# Sheet.net
KiCad netlist of a schematic drawn in Altium Designer
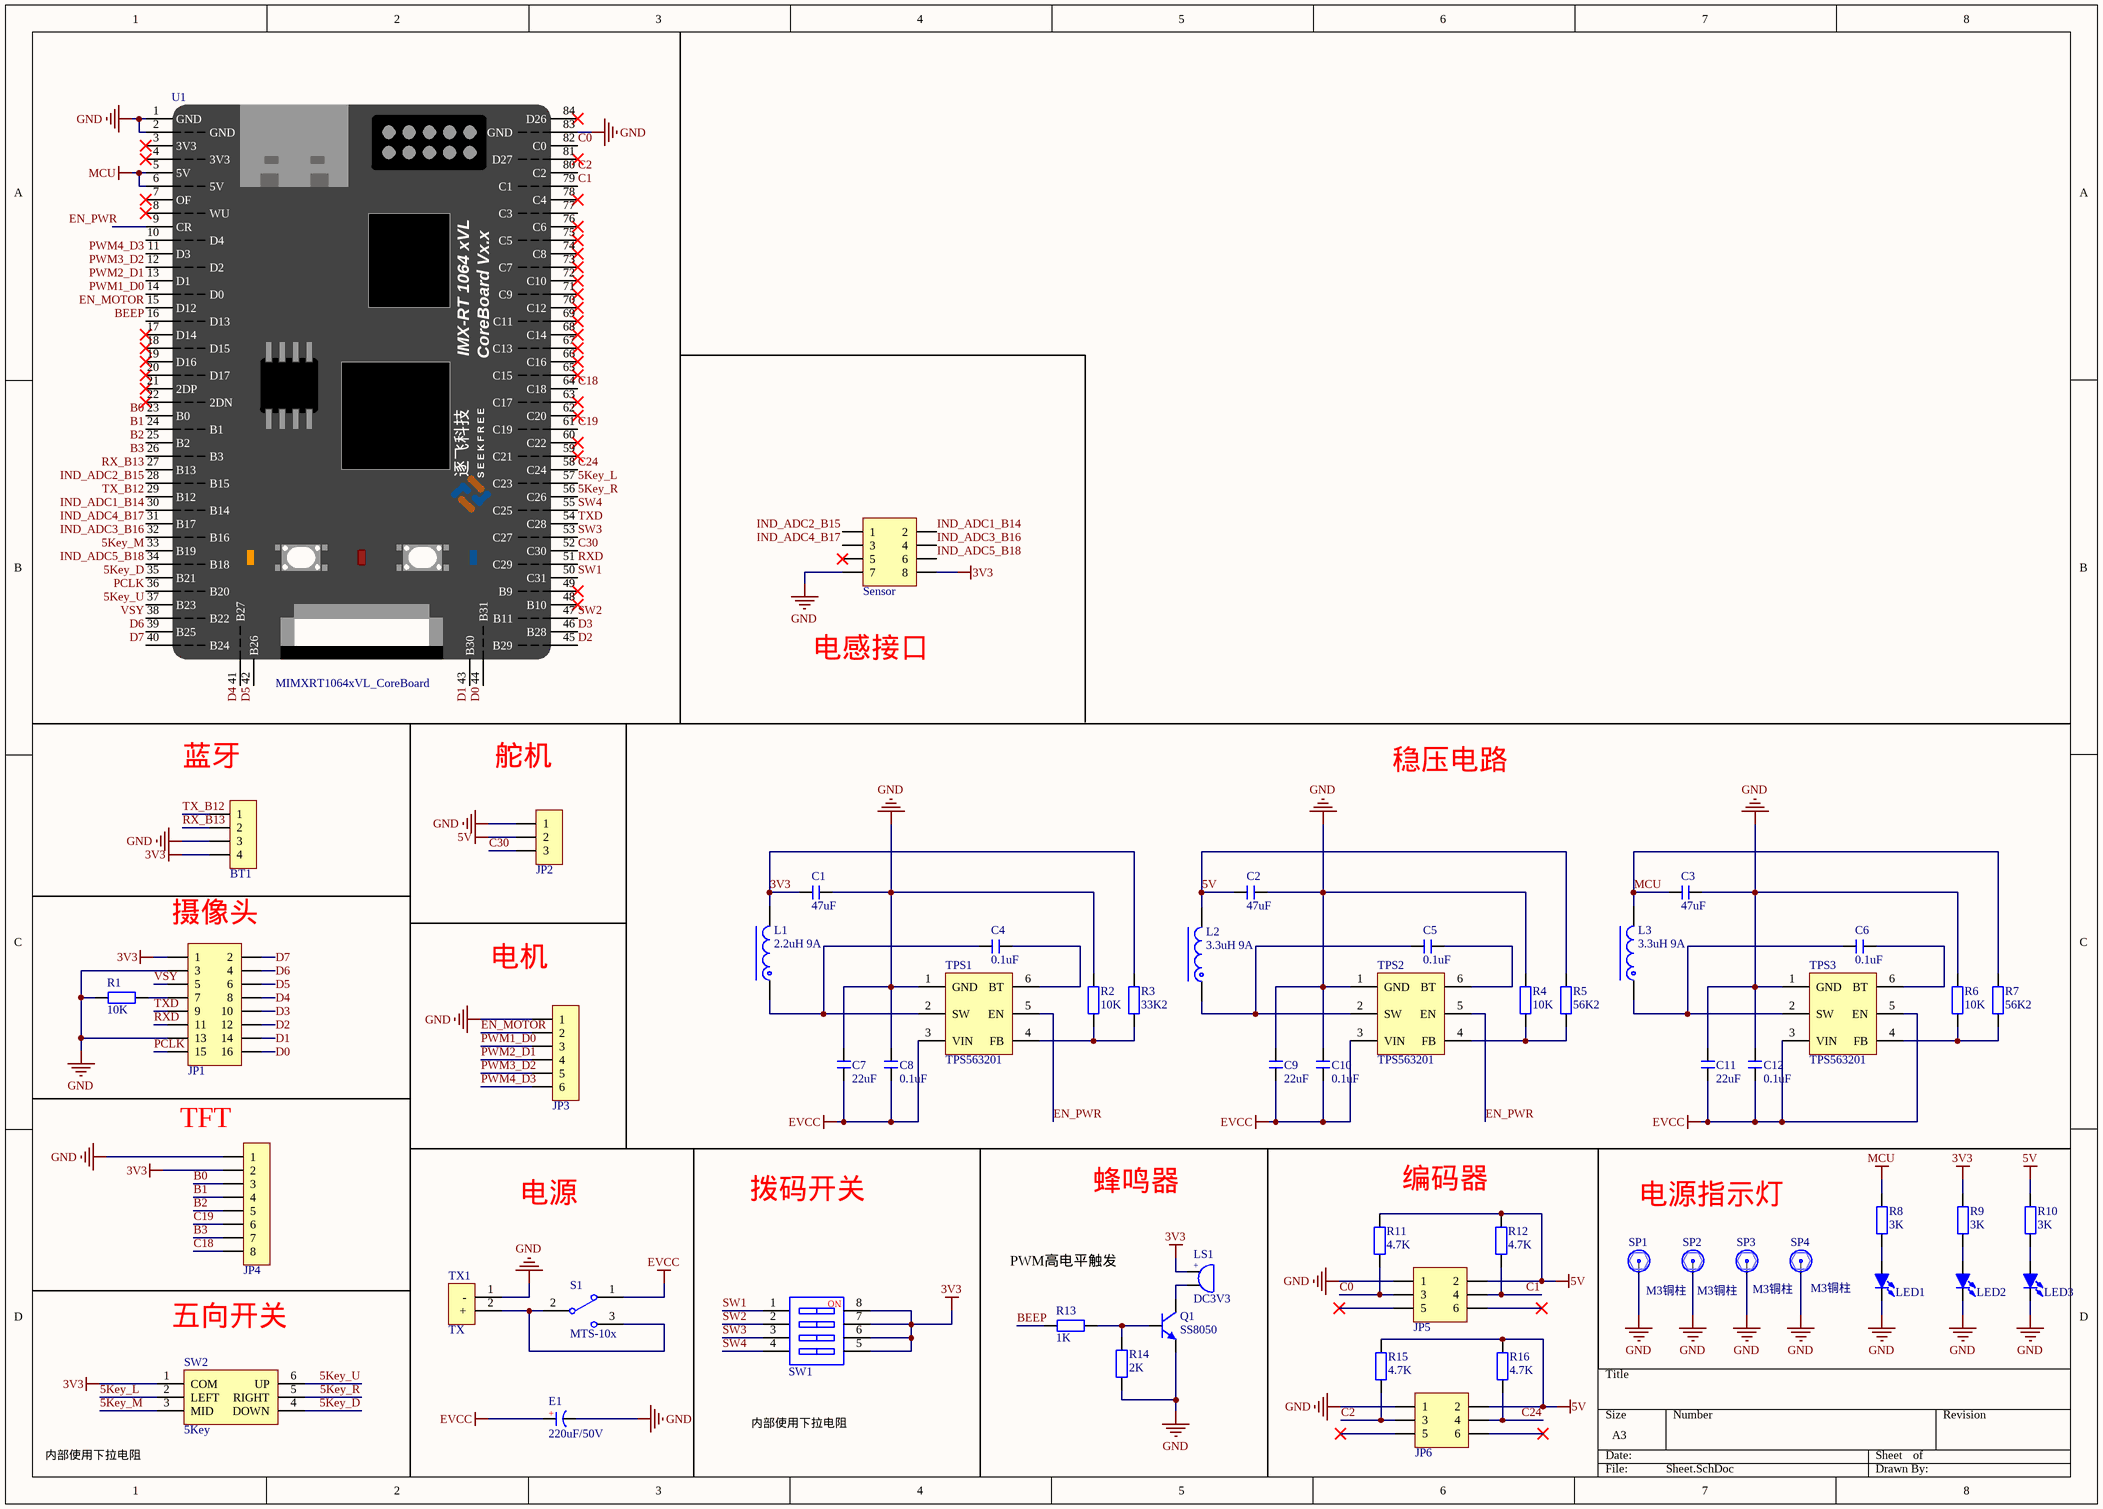
[diagram p0: Sheet.SchDoc]

(export (version "E")
  (design (tool "Eeschema 10.0.6"))
  (components
    (comp (ref "BT1")
      (value "HDR-1X4")
      (footprint "HDR2.54-M-LI-4P")
      (description "4P接插件")
      (fields (field (name "版权归属") "源创客"))
      (libsource (lib "Schlib") (part "Header 4"))
    )
    (comp (ref "C1")
      (value "47uF")
      (footprint "C 1206_M")
      (description "无极性贴片电容")
      (fields (field (name "版权归属") "源创客"))
      (libsource (lib "Schlib") (part "C_2"))
    )
    (comp (ref "C2")
      (value "47uF")
      (footprint "C 1206_M")
      (description "无极性贴片电容")
      (fields (field (name "版权归属") "源创客"))
      (libsource (lib "Schlib") (part "C_2"))
    )
    (comp (ref "C3")
      (value "47uF")
      (footprint "C 1206_M")
      (description "无极性贴片电容")
      (fields (field (name "版权归属") "源创客"))
      (libsource (lib "Schlib") (part "C_2"))
    )
    (comp (ref "C4")
      (value "0.1uF")
      (footprint "C 0603_M")
      (description "无极性贴片电容")
      (fields (field (name "版权归属") "源创客"))
      (libsource (lib "Schlib") (part "C_1"))
    )
    (comp (ref "C5")
      (value "0.1uF")
      (footprint "C 0603_M")
      (description "无极性贴片电容")
      (fields (field (name "版权归属") "源创客"))
      (libsource (lib "Schlib") (part "C_1"))
    )
    (comp (ref "C6")
      (value "0.1uF")
      (footprint "C 0603_M")
      (description "无极性贴片电容")
      (fields (field (name "版权归属") "源创客"))
      (libsource (lib "Schlib") (part "C_1"))
    )
    (comp (ref "C7")
      (value "22uF")
      (footprint "C 1206_M")
      (description "无极性贴片电容")
      (fields (field (name "版权归属") "源创客"))
      (libsource (lib "Schlib") (part "C"))
    )
    (comp (ref "C8")
      (value "0.1uF")
      (footprint "C 0603_M")
      (description "无极性贴片电容")
      (fields (field (name "版权归属") "源创客"))
      (libsource (lib "Schlib") (part "C_1"))
    )
    (comp (ref "C9")
      (value "22uF")
      (footprint "C 1206_M")
      (description "无极性贴片电容")
      (fields (field (name "版权归属") "源创客"))
      (libsource (lib "Schlib") (part "C"))
    )
    (comp (ref "C10")
      (value "0.1uF")
      (footprint "C 0603_M")
      (description "无极性贴片电容")
      (fields (field (name "版权归属") "源创客"))
      (libsource (lib "Schlib") (part "C_1"))
    )
    (comp (ref "C11")
      (value "22uF")
      (footprint "C 1206_M")
      (description "无极性贴片电容")
      (fields (field (name "版权归属") "源创客"))
      (libsource (lib "Schlib") (part "C"))
    )
    (comp (ref "C12")
      (value "0.1uF")
      (footprint "C 0603_M")
      (description "无极性贴片电容")
      (fields (field (name "版权归属") "源创客"))
      (libsource (lib "Schlib") (part "C_1"))
    )
    (comp (ref "E1")
      (value "220uF/50V")
      (footprint "CM F(10*10.2)")
      (description "贴片电解电容")
      (fields (field (name "版权归属") "源创客"))
      (libsource (lib "Schlib") (part "C-CM"))
    )
    (comp (ref "JP1")
      (value "Header 8X2")
      (footprint "HDR2.54-LI-2x8P")
      (description "8*2P接插件")
      (fields (field (name "版权归属") "源创客"))
      (libsource (lib "Schlib") (part "Header 8X2"))
    )
    (comp (ref "JP2")
      (value "HDR-1X3")
      (footprint "HDR2.54-WI-3P")
      (description "3P接插件")
      (fields (field (name "版权归属") "源创客"))
      (libsource (lib "Schlib") (part "Header 3"))
    )
    (comp (ref "JP3")
      (value "HDR-1X6")
      (footprint "HDR2.54-LI-6P")
      (description "6P接插件")
      (fields (field (name "版权归属") "源创客"))
      (libsource (lib "Schlib") (part "Header 6"))
    )
    (comp (ref "JP4")
      (value "HDR-1X8")
      (footprint "HDR2.54-M-LI-8P")
      (description "8P接插件")
      (fields (field (name "版权归属") "源创客"))
      (libsource (lib "Schlib") (part "Header 8"))
    )
    (comp (ref "JP5")
      (value "Header3X2")
      (footprint "HDR2.54-WI-2x3P")
      (description "3*2P接插件")
      (fields (field (name "版权归属") "源创客"))
      (libsource (lib "Schlib") (part "Header 3X2"))
    )
    (comp (ref "JP6")
      (value "Header3X2")
      (footprint "HDR2.54-WI-2x3P")
      (description "3*2P接插件")
      (fields (field (name "版权归属") "源创客"))
      (libsource (lib "Schlib") (part "Header 3X2"))
    )
    (comp (ref "L1")
      (value "2.2uH 9A")
      (footprint "L-SMD-0630")
      (description "功率屏蔽电感")
      (fields (field (name "版权归属") "源创客"))
      (libsource (lib "Schlib") (part "Inductor0630"))
    )
    (comp (ref "L2")
      (value "3.3uH 9A")
      (footprint "L-SMD-0630")
      (description "功率屏蔽电感")
      (fields (field (name "版权归属") "源创客"))
      (libsource (lib "Schlib") (part "Inductor0630_1"))
    )
    (comp (ref "L3")
      (value "3.3uH 9A")
      (footprint "L-SMD-0630")
      (description "功率屏蔽电感")
      (fields (field (name "版权归属") "源创客"))
      (libsource (lib "Schlib") (part "Inductor0630_1"))
    )
    (comp (ref "LED1")
      (value "红色")
      (footprint "LED 0805R")
      (description "贴片LED")
      (fields (field (name "版权归属") "源创客"))
      (libsource (lib "Schlib") (part "LED-SMD"))
    )
    (comp (ref "LED2")
      (value "红色")
      (footprint "LED 0805R")
      (description "贴片LED")
      (fields (field (name "版权归属") "源创客"))
      (libsource (lib "Schlib") (part "LED-SMD"))
    )
    (comp (ref "LED3")
      (value "红色")
      (footprint "LED 0805R")
      (description "贴片LED")
      (fields (field (name "版权归属") "源创客"))
      (libsource (lib "Schlib") (part "LED-SMD"))
    )
    (comp (ref "LS1")
      (value "DC3V3")
      (footprint "BEEP 4x9.6x5.5")
      (description "蜂鸣器")
      (fields (field (name "版权归属") "源创客"))
      (libsource (lib "Schlib") (part "BEEP"))
    )
    (comp (ref "Q1")
      (value "SS8050")
      (footprint "SOT23-3M")
      (description "高频放大-NPN型")
      (fields (field (name "版权归属") "源创客"))
      (libsource (lib "Schlib") (part "8050-SMD"))
    )
    (comp (ref "R1")
      (value "10K")
      (footprint "R 0603_M")
      (description "贴片电阻")
      (fields (field (name "版权归属") "源创客"))
      (libsource (lib "Schlib") (part "R_1"))
    )
    (comp (ref "R2")
      (value "10K")
      (footprint "R 0603_M")
      (description "贴片电阻")
      (fields (field (name "版权归属") "源创客"))
      (libsource (lib "Schlib") (part "R_1"))
    )
    (comp (ref "R3")
      (value "33K2")
      (footprint "R 0603_M")
      (description "贴片电阻")
      (fields (field (name "版权归属") "源创客"))
      (libsource (lib "Schlib") (part "R_2"))
    )
    (comp (ref "R4")
      (value "10K")
      (footprint "R 0603_M")
      (description "贴片电阻")
      (fields (field (name "版权归属") "源创客"))
      (libsource (lib "Schlib") (part "R_1"))
    )
    (comp (ref "R5")
      (value "56K2")
      (footprint "R 0603_M")
      (description "贴片电阻")
      (fields (field (name "版权归属") "源创客"))
      (libsource (lib "Schlib") (part "R_3"))
    )
    (comp (ref "R6")
      (value "10K")
      (footprint "R 0603_M")
      (description "贴片电阻")
      (fields (field (name "版权归属") "源创客"))
      (libsource (lib "Schlib") (part "R_1"))
    )
    (comp (ref "R7")
      (value "56K2")
      (footprint "R 0603_M")
      (description "贴片电阻")
      (fields (field (name "版权归属") "源创客"))
      (libsource (lib "Schlib") (part "R_3"))
    )
    (comp (ref "R8")
      (value "3K")
      (footprint "R 0603_M")
      (description "贴片电阻")
      (fields (field (name "版权归属") "源创客"))
      (libsource (lib "Schlib") (part "R_7"))
    )
    (comp (ref "R9")
      (value "3K")
      (footprint "R 0603_M")
      (description "贴片电阻")
      (fields (field (name "版权归属") "源创客"))
      (libsource (lib "Schlib") (part "R_7"))
    )
    (comp (ref "R10")
      (value "3K")
      (footprint "R 0603_M")
      (description "贴片电阻")
      (fields (field (name "版权归属") "源创客"))
      (libsource (lib "Schlib") (part "R_7"))
    )
    (comp (ref "R11")
      (value "4.7K")
      (footprint "R 0603_M")
      (description "贴片电阻")
      (fields (field (name "版权归属") "源创客"))
      (libsource (lib "Schlib") (part "R"))
    )
    (comp (ref "R12")
      (value "4.7K")
      (footprint "R 0603_M")
      (description "贴片电阻")
      (fields (field (name "版权归属") "源创客"))
      (libsource (lib "Schlib") (part "R"))
    )
    (comp (ref "R13")
      (value "1K")
      (footprint "R 0603_M")
      (description "贴片电阻")
      (fields (field (name "版权归属") "源创客"))
      (libsource (lib "Schlib") (part "R_5"))
    )
    (comp (ref "R14")
      (value "2K")
      (footprint "R 0603_M")
      (description "贴片电阻")
      (fields (field (name "版权归属") "源创客"))
      (libsource (lib "Schlib") (part "R_6"))
    )
    (comp (ref "R15")
      (value "4.7K")
      (footprint "R 0603_M")
      (description "贴片电阻")
      (fields (field (name "版权归属") "源创客"))
      (libsource (lib "Schlib") (part "R"))
    )
    (comp (ref "R16")
      (value "4.7K")
      (footprint "R 0603_M")
      (description "贴片电阻")
      (fields (field (name "版权归属") "源创客"))
      (libsource (lib "Schlib") (part "R"))
    )
    (comp (ref "S1")
      (value "MTS-10x")
      (footprint "MTS-10x")
      (description "MTS10x系列3脚扭子开关")
      (fields (field (name "版权归属") "源创客"))
      (libsource (lib "Schlib") (part "MTS-10x"))
    )
    (comp (ref "Sensor")
      (value "Header 4X2")
      (footprint "HDR-4X2")
      (description "4*2P接插件")
      (fields (field (name "版权归属") "源创客"))
      (libsource (lib "Schlib") (part "Header 4X2"))
    )
    (comp (ref "SP1")
      (value "M3铜柱")
      (footprint "M3x4_L")
      (description "铜柱")
      (fields (field (name "版权归属") "源创客"))
      (libsource (lib "Schlib") (part "铜柱小焊盘"))
    )
    (comp (ref "SP2")
      (value "M3铜柱")
      (footprint "M3x4_L")
      (description "铜柱")
      (fields (field (name "版权归属") "源创客"))
      (libsource (lib "Schlib") (part "铜柱小焊盘"))
    )
    (comp (ref "SP3")
      (value "M3铜柱")
      (footprint "M3x4_L")
      (description "铜柱")
      (fields (field (name "版权归属") "源创客"))
      (libsource (lib "Schlib") (part "铜柱小焊盘"))
    )
    (comp (ref "SP4")
      (value "M3铜柱")
      (footprint "M3x4_L")
      (description "铜柱")
      (fields (field (name "版权归属") "源创客"))
      (libsource (lib "Schlib") (part "铜柱小焊盘"))
    )
    (comp (ref "SW1")
      (value "CSW-4P")
      (footprint "CSW DIP-4P_G")
      (description "4路编码开关")
      (fields (field (name "版权归属") "源创客"))
      (libsource (lib "Schlib") (part "CSW-4P"))
    )
    (comp (ref "SW2")
      (value "5Key")
      (footprint "TSW 10x10x9-5Key-LS")
      (libsource (lib "Schlib") (part "5Key"))
    )
    (comp (ref "TPS1")
      (value "TPS563201")
      (footprint "SOT23-6N")
      (libsource (lib "Schlib") (part "TPS54302"))
    )
    (comp (ref "TPS2")
      (value "TPS563201")
      (footprint "SOT23-6N")
      (libsource (lib "Schlib") (part "TPS54302"))
    )
    (comp (ref "TPS3")
      (value "TPS563201")
      (footprint "SOT23-6N")
      (libsource (lib "Schlib") (part "TPS54302"))
    )
    (comp (ref "TX1") (value "TX") (footprint "TX") (libsource (lib "Schlib") (part "T型插头")))
    (comp (ref "U1")
      (value "MIMXRT1064xVL_CoreBoard")
      (footprint "MIMXRT1064xVL_CoreBoard")
      (description "逐飞科技i.MX RT1064核心板整体原理，可直接使用")
      (libsource (lib "RT1064 V1.2") (part "MIMXRT1064xVL_CoreBoard"))
    )
  )
  (nets
    (net (code "1") (name "/5Key_D") (class "Default")
      (node (ref "SW2") (pin "4") (pinfunction "DOWN_4") (pintype "passive"))
      (node (ref "U1") (pin "35") (pinfunction "B21_35") (pintype "passive"))
    )
    (net (code "2") (name "/5Key_L") (class "Default")
      (node (ref "SW2") (pin "2") (pinfunction "LEFT_2") (pintype "passive"))
      (node (ref "U1") (pin "57") (pinfunction "C23_57") (pintype "passive"))
    )
    (net (code "3") (name "/5Key_M") (class "Default")
      (node (ref "SW2") (pin "3") (pinfunction "MID_3") (pintype "passive"))
      (node (ref "U1") (pin "33") (pinfunction "B19_33") (pintype "passive"))
    )
    (net (code "4") (name "/5Key_R") (class "Default")
      (node (ref "SW2") (pin "5") (pinfunction "RIGHT_5") (pintype "passive"))
      (node (ref "U1") (pin "56") (pinfunction "C26_56") (pintype "passive"))
    )
    (net (code "5") (name "/5Key_U") (class "Default")
      (node (ref "SW2") (pin "6") (pinfunction "UP_6") (pintype "passive"))
      (node (ref "U1") (pin "37") (pinfunction "B23_37") (pintype "passive"))
    )
    (net (code "6") (name "/B0") (class "Default")
      (node (ref "JP4") (pin "3") (pinfunction "3_3") (pintype "passive"))
      (node (ref "U1") (pin "23") (pinfunction "B0_23") (pintype "passive"))
    )
    (net (code "7") (name "/B1") (class "Default")
      (node (ref "JP4") (pin "4") (pinfunction "4_4") (pintype "passive"))
      (node (ref "U1") (pin "24") (pinfunction "B1_24") (pintype "passive"))
    )
    (net (code "8") (name "/B2") (class "Default")
      (node (ref "JP4") (pin "5") (pinfunction "5_5") (pintype "passive"))
      (node (ref "U1") (pin "25") (pinfunction "B2_25") (pintype "passive"))
    )
    (net (code "9") (name "/B3") (class "Default")
      (node (ref "JP4") (pin "7") (pinfunction "7_7") (pintype "passive"))
      (node (ref "U1") (pin "26") (pinfunction "B3_26") (pintype "passive"))
    )
    (net (code "10") (name "/BEEP") (class "Default")
      (node (ref "R13") (pin "1") (pinfunction "1_1") (pintype "passive"))
      (node (ref "U1") (pin "16") (pinfunction "D13_16") (pintype "passive"))
    )
    (net (code "11") (name "/C0") (class "Default")
      (node (ref "JP5") (pin "3") (pinfunction "3_3") (pintype "passive"))
      (node (ref "R11") (pin "1") (pinfunction "1_1") (pintype "passive"))
      (node (ref "U1") (pin "82") (pinfunction "C0_82") (pintype "passive"))
    )
    (net (code "12") (name "/C1") (class "Default")
      (node (ref "JP5") (pin "4") (pinfunction "4_4") (pintype "passive"))
      (node (ref "R12") (pin "1") (pinfunction "1_1") (pintype "passive"))
      (node (ref "U1") (pin "79") (pinfunction "C1_79") (pintype "passive"))
    )
    (net (code "13") (name "/C2") (class "Default")
      (node (ref "JP6") (pin "3") (pinfunction "3_3") (pintype "passive"))
      (node (ref "R15") (pin "1") (pinfunction "1_1") (pintype "passive"))
      (node (ref "U1") (pin "80") (pinfunction "C2_80") (pintype "passive"))
    )
    (net (code "14") (name "/C18") (class "Default")
      (node (ref "JP4") (pin "8") (pinfunction "8_8") (pintype "passive"))
      (node (ref "U1") (pin "64") (pinfunction "C18_64") (pintype "passive"))
    )
    (net (code "15") (name "/C19") (class "Default")
      (node (ref "JP4") (pin "6") (pinfunction "6_6") (pintype "passive"))
      (node (ref "U1") (pin "61") (pinfunction "C19_61") (pintype "passive"))
    )
    (net (code "16") (name "/C24") (class "Default")
      (node (ref "JP6") (pin "4") (pinfunction "4_4") (pintype "passive"))
      (node (ref "R16") (pin "1") (pinfunction "1_1") (pintype "passive"))
      (node (ref "U1") (pin "58") (pinfunction "C24_58") (pintype "passive"))
    )
    (net (code "17") (name "/C30") (class "Default")
      (node (ref "JP2") (pin "3") (pinfunction "3_3") (pintype "passive"))
      (node (ref "U1") (pin "52") (pinfunction "C30_52") (pintype "passive"))
    )
    (net (code "18") (name "/D0") (class "Default")
      (node (ref "JP1") (pin "16") (pinfunction "16_16") (pintype "passive"))
      (node (ref "U1") (pin "44") (pinfunction "B31_44") (pintype "passive"))
    )
    (net (code "19") (name "/D1") (class "Default")
      (node (ref "JP1") (pin "14") (pinfunction "14_14") (pintype "passive"))
      (node (ref "U1") (pin "43") (pinfunction "B30_43") (pintype "passive"))
    )
    (net (code "20") (name "/D2") (class "Default")
      (node (ref "JP1") (pin "12") (pinfunction "12_12") (pintype "passive"))
      (node (ref "U1") (pin "45") (pinfunction "B29_45") (pintype "passive"))
    )
    (net (code "21") (name "/D3") (class "Default")
      (node (ref "JP1") (pin "10") (pinfunction "10_10") (pintype "passive"))
      (node (ref "U1") (pin "46") (pinfunction "B28_46") (pintype "passive"))
    )
    (net (code "22") (name "/D4") (class "Default")
      (node (ref "JP1") (pin "8") (pinfunction "8_8") (pintype "passive"))
      (node (ref "U1") (pin "41") (pinfunction "B27_41") (pintype "passive"))
    )
    (net (code "23") (name "/D5") (class "Default")
      (node (ref "JP1") (pin "6") (pinfunction "6_6") (pintype "passive"))
      (node (ref "U1") (pin "42") (pinfunction "B26_42") (pintype "passive"))
    )
    (net (code "24") (name "/D6") (class "Default")
      (node (ref "JP1") (pin "4") (pinfunction "4_4") (pintype "passive"))
      (node (ref "U1") (pin "39") (pinfunction "B25_39") (pintype "passive"))
    )
    (net (code "25") (name "/D7") (class "Default")
      (node (ref "JP1") (pin "2") (pinfunction "2_2") (pintype "passive"))
      (node (ref "U1") (pin "40") (pinfunction "B24_40") (pintype "passive"))
    )
    (net (code "26") (name "/EN_MOTOR") (class "Default")
      (node (ref "JP3") (pin "2") (pinfunction "2_2") (pintype "passive"))
      (node (ref "U1") (pin "15") (pinfunction "D12_15") (pintype "passive"))
    )
    (net (code "27") (name "/EN_PWR") (class "Default")
      (node (ref "TPS1") (pin "5") (pinfunction "EN_5") (pintype "passive"))
      (node (ref "TPS2") (pin "5") (pinfunction "EN_5") (pintype "passive"))
      (node (ref "U1") (pin "9") (pinfunction "CR_9") (pintype "passive"))
    )
    (net (code "28") (name "/IND_ADC1_B14") (class "Default")
      (node (ref "Sensor") (pin "2") (pinfunction "2_2") (pintype "passive"))
      (node (ref "U1") (pin "30") (pinfunction "B14_30") (pintype "passive"))
    )
    (net (code "29") (name "/IND_ADC2_B15") (class "Default")
      (node (ref "Sensor") (pin "1") (pinfunction "1_1") (pintype "passive"))
      (node (ref "U1") (pin "28") (pinfunction "B15_28") (pintype "passive"))
    )
    (net (code "30") (name "/IND_ADC3_B16") (class "Default")
      (node (ref "Sensor") (pin "4") (pinfunction "4_4") (pintype "passive"))
      (node (ref "U1") (pin "32") (pinfunction "B16_32") (pintype "passive"))
    )
    (net (code "31") (name "/IND_ADC4_B17") (class "Default")
      (node (ref "Sensor") (pin "3") (pinfunction "3_3") (pintype "passive"))
      (node (ref "U1") (pin "31") (pinfunction "B17_31") (pintype "passive"))
    )
    (net (code "32") (name "/IND_ADC5_B18") (class "Default")
      (node (ref "Sensor") (pin "6") (pinfunction "6_6") (pintype "passive"))
      (node (ref "U1") (pin "34") (pinfunction "B18_34") (pintype "passive"))
    )
    (net (code "33") (name "/PCLK") (class "Default")
      (node (ref "JP1") (pin "15") (pinfunction "15_15") (pintype "passive"))
      (node (ref "U1") (pin "36") (pinfunction "B20_36") (pintype "passive"))
    )
    (net (code "34") (name "/PWM1_D0") (class "Default")
      (node (ref "JP3") (pin "3") (pinfunction "3_3") (pintype "passive"))
      (node (ref "U1") (pin "14") (pinfunction "D0_14") (pintype "passive"))
    )
    (net (code "35") (name "/PWM2_D1") (class "Default")
      (node (ref "JP3") (pin "4") (pinfunction "4_4") (pintype "passive"))
      (node (ref "U1") (pin "13") (pinfunction "D1_13") (pintype "passive"))
    )
    (net (code "36") (name "/PWM3_D2") (class "Default")
      (node (ref "JP3") (pin "5") (pinfunction "5_5") (pintype "passive"))
      (node (ref "U1") (pin "12") (pinfunction "D2_12") (pintype "passive"))
    )
    (net (code "37") (name "/PWM4_D3") (class "Default")
      (node (ref "JP3") (pin "6") (pinfunction "6_6") (pintype "passive"))
      (node (ref "U1") (pin "11") (pinfunction "D3_11") (pintype "passive"))
    )
    (net (code "38") (name "/RXD") (class "Default")
      (node (ref "JP1") (pin "11") (pinfunction "11_11") (pintype "passive"))
      (node (ref "U1") (pin "51") (pinfunction "C29_51") (pintype "passive"))
    )
    (net (code "39") (name "/RX_B13") (class "Default")
      (node (ref "BT1") (pin "2") (pinfunction "2_2") (pintype "passive"))
      (node (ref "U1") (pin "27") (pinfunction "B13_27") (pintype "passive"))
    )
    (net (code "40") (name "/SW1") (class "Default")
      (node (ref "SW1") (pin "1") (pinfunction "1_1") (pintype "passive"))
      (node (ref "U1") (pin "50") (pinfunction "C31_50") (pintype "passive"))
    )
    (net (code "41") (name "/SW2") (class "Default")
      (node (ref "SW1") (pin "2") (pinfunction "2_2") (pintype "passive"))
      (node (ref "U1") (pin "47") (pinfunction "B11_47") (pintype "passive"))
    )
    (net (code "42") (name "/SW3") (class "Default")
      (node (ref "SW1") (pin "3") (pinfunction "3_3") (pintype "passive"))
      (node (ref "U1") (pin "53") (pinfunction "C27_53") (pintype "passive"))
    )
    (net (code "43") (name "/SW4") (class "Default")
      (node (ref "SW1") (pin "4") (pinfunction "4_4") (pintype "passive"))
      (node (ref "U1") (pin "55") (pinfunction "C25_55") (pintype "passive"))
    )
    (net (code "44") (name "/TXD") (class "Default")
      (node (ref "JP1") (pin "9") (pinfunction "9_9") (pintype "passive"))
      (node (ref "U1") (pin "54") (pinfunction "C28_54") (pintype "passive"))
    )
    (net (code "45") (name "/TX_B12") (class "Default")
      (node (ref "BT1") (pin "1") (pinfunction "1_1") (pintype "passive"))
      (node (ref "U1") (pin "29") (pinfunction "B12_29") (pintype "passive"))
    )
    (net (code "46") (name "/VSY") (class "Default")
      (node (ref "JP1") (pin "5") (pinfunction "5_5") (pintype "passive"))
      (node (ref "U1") (pin "38") (pinfunction "B22_38") (pintype "passive"))
    )
    (net (code "47") (name "3V3") (class "Default")
      (node (ref "BT1") (pin "4") (pinfunction "4_4") (pintype "passive"))
      (node (ref "C1") (pin "1") (pinfunction "1_1") (pintype "passive"))
      (node (ref "JP1") (pin "1") (pinfunction "1_1") (pintype "passive"))
      (node (ref "JP4") (pin "2") (pinfunction "2_2") (pintype "passive"))
      (node (ref "L1") (pin "2") (pinfunction "2_2") (pintype "passive"))
      (node (ref "LS1") (pin "1") (pinfunction "1_1") (pintype "passive"))
      (node (ref "R3") (pin "2") (pinfunction "2_2") (pintype "passive"))
      (node (ref "R9") (pin "2") (pinfunction "2_2") (pintype "passive"))
      (node (ref "SW1") (pin "5") (pinfunction "5_5") (pintype "passive"))
      (node (ref "SW1") (pin "6") (pinfunction "6_6") (pintype "passive"))
      (node (ref "SW1") (pin "7") (pinfunction "7_7") (pintype "passive"))
      (node (ref "SW1") (pin "8") (pinfunction "8_8") (pintype "passive"))
      (node (ref "SW2") (pin "1") (pinfunction "COM_1") (pintype "passive"))
      (node (ref "Sensor") (pin "8") (pinfunction "8_8") (pintype "passive"))
    )
    (net (code "48") (name "5V") (class "Default")
      (node (ref "C2") (pin "1") (pinfunction "1_1") (pintype "passive"))
      (node (ref "JP2") (pin "2") (pinfunction "2_2") (pintype "passive"))
      (node (ref "JP5") (pin "2") (pinfunction "2_2") (pintype "passive"))
      (node (ref "JP6") (pin "2") (pinfunction "2_2") (pintype "passive"))
      (node (ref "L2") (pin "2") (pinfunction "2_2") (pintype "passive"))
      (node (ref "R10") (pin "2") (pinfunction "2_2") (pintype "passive"))
      (node (ref "R11") (pin "2") (pinfunction "2_2") (pintype "passive"))
      (node (ref "R12") (pin "2") (pinfunction "2_2") (pintype "passive"))
      (node (ref "R15") (pin "2") (pinfunction "2_2") (pintype "passive"))
      (node (ref "R16") (pin "2") (pinfunction "2_2") (pintype "passive"))
      (node (ref "R5") (pin "2") (pinfunction "2_2") (pintype "passive"))
    )
    (net (code "49") (name "EVCC") (class "Default")
      (node (ref "C10") (pin "1") (pinfunction "1_1") (pintype "passive"))
      (node (ref "C11") (pin "1") (pinfunction "1_1") (pintype "passive"))
      (node (ref "C12") (pin "1") (pinfunction "1_1") (pintype "passive"))
      (node (ref "C7") (pin "1") (pinfunction "1_1") (pintype "passive"))
      (node (ref "C8") (pin "1") (pinfunction "1_1") (pintype "passive"))
      (node (ref "C9") (pin "1") (pinfunction "1_1") (pintype "passive"))
      (node (ref "E1") (pin "1") (pinfunction "A_1") (pintype "passive"))
      (node (ref "S1") (pin "1") (pinfunction "1_1") (pintype "passive"))
      (node (ref "TPS1") (pin "3") (pinfunction "VIN_3") (pintype "passive"))
      (node (ref "TPS2") (pin "3") (pinfunction "VIN_3") (pintype "passive"))
      (node (ref "TPS3") (pin "3") (pinfunction "VIN_3") (pintype "passive"))
      (node (ref "TPS3") (pin "5") (pinfunction "EN_5") (pintype "passive"))
    )
    (net (code "50") (name "GND") (class "Default")
      (node (ref "BT1") (pin "3") (pinfunction "3_3") (pintype "passive"))
      (node (ref "C1") (pin "2") (pinfunction "2_2") (pintype "passive"))
      (node (ref "C10") (pin "2") (pinfunction "2_2") (pintype "passive"))
      (node (ref "C11") (pin "2") (pinfunction "2_2") (pintype "passive"))
      (node (ref "C12") (pin "2") (pinfunction "2_2") (pintype "passive"))
      (node (ref "C2") (pin "2") (pinfunction "2_2") (pintype "passive"))
      (node (ref "C3") (pin "2") (pinfunction "2_2") (pintype "passive"))
      (node (ref "C7") (pin "2") (pinfunction "2_2") (pintype "passive"))
      (node (ref "C8") (pin "2") (pinfunction "2_2") (pintype "passive"))
      (node (ref "C9") (pin "2") (pinfunction "2_2") (pintype "passive"))
      (node (ref "E1") (pin "2") (pinfunction "K_2") (pintype "passive"))
      (node (ref "JP1") (pin "13") (pinfunction "13_13") (pintype "passive"))
      (node (ref "JP1") (pin "3") (pinfunction "3_3") (pintype "passive"))
      (node (ref "JP2") (pin "1") (pinfunction "1_1") (pintype "passive"))
      (node (ref "JP3") (pin "1") (pinfunction "1_1") (pintype "passive"))
      (node (ref "JP4") (pin "1") (pinfunction "1_1") (pintype "passive"))
      (node (ref "JP5") (pin "1") (pinfunction "1_1") (pintype "passive"))
      (node (ref "JP6") (pin "1") (pinfunction "1_1") (pintype "passive"))
      (node (ref "LED1") (pin "2") (pinfunction "K_2") (pintype "passive"))
      (node (ref "LED2") (pin "2") (pinfunction "K_2") (pintype "passive"))
      (node (ref "LED3") (pin "2") (pinfunction "K_2") (pintype "passive"))
      (node (ref "Q1") (pin "2") (pinfunction "E_2") (pintype "passive"))
      (node (ref "R1") (pin "1") (pinfunction "1_1") (pintype "passive"))
      (node (ref "R14") (pin "1") (pinfunction "1_1") (pintype "passive"))
      (node (ref "R2") (pin "2") (pinfunction "2_2") (pintype "passive"))
      (node (ref "R4") (pin "2") (pinfunction "2_2") (pintype "passive"))
      (node (ref "R6") (pin "2") (pinfunction "2_2") (pintype "passive"))
      (node (ref "SP1") (pin "1") (pinfunction "1_1") (pintype "passive"))
      (node (ref "SP2") (pin "1") (pinfunction "1_1") (pintype "passive"))
      (node (ref "SP3") (pin "1") (pinfunction "1_1") (pintype "passive"))
      (node (ref "SP4") (pin "1") (pinfunction "1_1") (pintype "passive"))
      (node (ref "Sensor") (pin "7") (pinfunction "7_7") (pintype "passive"))
      (node (ref "TPS1") (pin "1") (pinfunction "GND_1") (pintype "passive"))
      (node (ref "TPS2") (pin "1") (pinfunction "GND_1") (pintype "passive"))
      (node (ref "TPS3") (pin "1") (pinfunction "GND_1") (pintype "passive"))
      (node (ref "TX1") (pin "1") (pinfunction "-_1") (pintype "passive"))
      (node (ref "U1") (pin "1") (pinfunction "GND_1") (pintype "passive"))
      (node (ref "U1") (pin "2") (pinfunction "GND_2") (pintype "passive"))
      (node (ref "U1") (pin "83") (pinfunction "GND_83") (pintype "passive"))
    )
    (net (code "51") (name "MCU") (class "Default")
      (node (ref "C3") (pin "1") (pinfunction "1_1") (pintype "passive"))
      (node (ref "L3") (pin "2") (pinfunction "2_2") (pintype "passive"))
      (node (ref "R7") (pin "2") (pinfunction "2_2") (pintype "passive"))
      (node (ref "R8") (pin "2") (pinfunction "2_2") (pintype "passive"))
      (node (ref "U1") (pin "5") (pinfunction "5V_5") (pintype "passive"))
      (node (ref "U1") (pin "6") (pinfunction "5V_6") (pintype "passive"))
    )
    (net (code "52") (name "Net-(JP1-Pad7)") (class "Default")
      (node (ref "JP1") (pin "7") (pinfunction "7_7") (pintype "passive"))
      (node (ref "R1") (pin "2") (pinfunction "2_2") (pintype "passive"))
    )
    (net (code "53") (name "Net-(LED1-A)") (class "Default")
      (node (ref "LED1") (pin "1") (pinfunction "A_1") (pintype "passive"))
      (node (ref "R8") (pin "1") (pinfunction "1_1") (pintype "passive"))
    )
    (net (code "54") (name "Net-(LED2-A)") (class "Default")
      (node (ref "LED2") (pin "1") (pinfunction "A_1") (pintype "passive"))
      (node (ref "R9") (pin "1") (pinfunction "1_1") (pintype "passive"))
    )
    (net (code "55") (name "Net-(LED3-A)") (class "Default")
      (node (ref "LED3") (pin "1") (pinfunction "A_1") (pintype "passive"))
      (node (ref "R10") (pin "1") (pinfunction "1_1") (pintype "passive"))
    )
    (net (code "56") (name "Net-(Q1-B)") (class "Default")
      (node (ref "Q1") (pin "1") (pinfunction "B_1") (pintype "passive"))
      (node (ref "R13") (pin "2") (pinfunction "2_2") (pintype "passive"))
      (node (ref "R14") (pin "2") (pinfunction "2_2") (pintype "passive"))
    )
    (net (code "57") (name "Net-(Q1-C)") (class "Default")
      (node (ref "LS1") (pin "2") (pinfunction "2_2") (pintype "passive"))
      (node (ref "Q1") (pin "3") (pinfunction "C_3") (pintype "passive"))
    )
    (net (code "58") (name "Net-(TPS1-BT)") (class "Default")
      (node (ref "C4") (pin "2") (pinfunction "2_2") (pintype "passive"))
      (node (ref "TPS1") (pin "6") (pinfunction "BT_6") (pintype "passive"))
    )
    (net (code "59") (name "Net-(TPS1-FB)") (class "Default")
      (node (ref "R2") (pin "1") (pinfunction "1_1") (pintype "passive"))
      (node (ref "R3") (pin "1") (pinfunction "1_1") (pintype "passive"))
      (node (ref "TPS1") (pin "4") (pinfunction "FB_4") (pintype "passive"))
    )
    (net (code "60") (name "Net-(TPS1-SW)") (class "Default")
      (node (ref "C4") (pin "1") (pinfunction "1_1") (pintype "passive"))
      (node (ref "L1") (pin "1") (pinfunction "1_1") (pintype "passive"))
      (node (ref "TPS1") (pin "2") (pinfunction "SW_2") (pintype "passive"))
    )
    (net (code "61") (name "Net-(TPS2-BT)") (class "Default")
      (node (ref "C5") (pin "2") (pinfunction "2_2") (pintype "passive"))
      (node (ref "TPS2") (pin "6") (pinfunction "BT_6") (pintype "passive"))
    )
    (net (code "62") (name "Net-(TPS2-FB)") (class "Default")
      (node (ref "R4") (pin "1") (pinfunction "1_1") (pintype "passive"))
      (node (ref "R5") (pin "1") (pinfunction "1_1") (pintype "passive"))
      (node (ref "TPS2") (pin "4") (pinfunction "FB_4") (pintype "passive"))
    )
    (net (code "63") (name "Net-(TPS2-SW)") (class "Default")
      (node (ref "C5") (pin "1") (pinfunction "1_1") (pintype "passive"))
      (node (ref "L2") (pin "1") (pinfunction "1_1") (pintype "passive"))
      (node (ref "TPS2") (pin "2") (pinfunction "SW_2") (pintype "passive"))
    )
    (net (code "64") (name "Net-(TPS3-BT)") (class "Default")
      (node (ref "C6") (pin "2") (pinfunction "2_2") (pintype "passive"))
      (node (ref "TPS3") (pin "6") (pinfunction "BT_6") (pintype "passive"))
    )
    (net (code "65") (name "Net-(TPS3-FB)") (class "Default")
      (node (ref "R6") (pin "1") (pinfunction "1_1") (pintype "passive"))
      (node (ref "R7") (pin "1") (pinfunction "1_1") (pintype "passive"))
      (node (ref "TPS3") (pin "4") (pinfunction "FB_4") (pintype "passive"))
    )
    (net (code "66") (name "Net-(TPS3-SW)") (class "Default")
      (node (ref "C6") (pin "1") (pinfunction "1_1") (pintype "passive"))
      (node (ref "L3") (pin "1") (pinfunction "1_1") (pintype "passive"))
      (node (ref "TPS3") (pin "2") (pinfunction "SW_2") (pintype "passive"))
    )
    (net (code "67") (name "Net-(TX1-+)") (class "Default")
      (node (ref "S1") (pin "2") (pinfunction "2_2") (pintype "passive"))
      (node (ref "S1") (pin "3") (pinfunction "3_3") (pintype "passive"))
      (node (ref "TX1") (pin "2") (pinfunction "+_2") (pintype "passive"))
    )
    (net (code "68") (name "unconnected-(JP5-Pad5)") (class "Default")
      (node (ref "JP5") (pin "5") (pinfunction "5_5") (pintype "passive+no_connect"))
    )
    (net (code "69") (name "unconnected-(JP5-Pad6)") (class "Default")
      (node (ref "JP5") (pin "6") (pinfunction "6_6") (pintype "passive+no_connect"))
    )
    (net (code "70") (name "unconnected-(JP6-Pad5)") (class "Default")
      (node (ref "JP6") (pin "5") (pinfunction "5_5") (pintype "passive+no_connect"))
    )
    (net (code "71") (name "unconnected-(JP6-Pad6)") (class "Default")
      (node (ref "JP6") (pin "6") (pinfunction "6_6") (pintype "passive+no_connect"))
    )
    (net (code "72") (name "unconnected-(Sensor-Pad5)") (class "Default")
      (node (ref "Sensor") (pin "5") (pinfunction "5_5") (pintype "passive+no_connect"))
    )
    (net (code "73") (name "unconnected-(U1-2DN-Pad22)") (class "Default")
      (node (ref "U1") (pin "22") (pinfunction "2DN_22") (pintype "passive+no_connect"))
    )
    (net (code "74") (name "unconnected-(U1-2DP-Pad21)") (class "Default")
      (node (ref "U1") (pin "21") (pinfunction "2DP_21") (pintype "passive+no_connect"))
    )
    (net (code "75") (name "unconnected-(U1-3V3-Pad3)") (class "Default")
      (node (ref "U1") (pin "3") (pinfunction "3V3_3") (pintype "passive+no_connect"))
    )
    (net (code "76") (name "unconnected-(U1-3V3-Pad4)") (class "Default")
      (node (ref "U1") (pin "4") (pinfunction "3V3_4") (pintype "passive+no_connect"))
    )
    (net (code "77") (name "unconnected-(U1-B9-Pad49)") (class "Default")
      (node (ref "U1") (pin "49") (pinfunction "B9_49") (pintype "passive+no_connect"))
    )
    (net (code "78") (name "unconnected-(U1-B10-Pad48)") (class "Default")
      (node (ref "U1") (pin "48") (pinfunction "B10_48") (pintype "passive+no_connect"))
    )
    (net (code "79") (name "unconnected-(U1-C3-Pad77)") (class "Default")
      (node (ref "U1") (pin "77") (pinfunction "C3_77") (pintype "passive"))
    )
    (net (code "80") (name "unconnected-(U1-C4-Pad78)") (class "Default")
      (node (ref "U1") (pin "78") (pinfunction "C4_78") (pintype "passive+no_connect"))
    )
    (net (code "81") (name "unconnected-(U1-C5-Pad75)") (class "Default")
      (node (ref "U1") (pin "75") (pinfunction "C5_75") (pintype "passive+no_connect"))
    )
    (net (code "82") (name "unconnected-(U1-C6-Pad76)") (class "Default")
      (node (ref "U1") (pin "76") (pinfunction "C6_76") (pintype "passive+no_connect"))
    )
    (net (code "83") (name "unconnected-(U1-C7-Pad73)") (class "Default")
      (node (ref "U1") (pin "73") (pinfunction "C7_73") (pintype "passive+no_connect"))
    )
    (net (code "84") (name "unconnected-(U1-C8-Pad74)") (class "Default")
      (node (ref "U1") (pin "74") (pinfunction "C8_74") (pintype "passive+no_connect"))
    )
    (net (code "85") (name "unconnected-(U1-C9-Pad71)") (class "Default")
      (node (ref "U1") (pin "71") (pinfunction "C9_71") (pintype "passive+no_connect"))
    )
    (net (code "86") (name "unconnected-(U1-C10-Pad72)") (class "Default")
      (node (ref "U1") (pin "72") (pinfunction "C10_72") (pintype "passive+no_connect"))
    )
    (net (code "87") (name "unconnected-(U1-C11-Pad69)") (class "Default")
      (node (ref "U1") (pin "69") (pinfunction "C11_69") (pintype "passive+no_connect"))
    )
    (net (code "88") (name "unconnected-(U1-C12-Pad70)") (class "Default")
      (node (ref "U1") (pin "70") (pinfunction "C12_70") (pintype "passive+no_connect"))
    )
    (net (code "89") (name "unconnected-(U1-C13-Pad67)") (class "Default")
      (node (ref "U1") (pin "67") (pinfunction "C13_67") (pintype "passive+no_connect"))
    )
    (net (code "90") (name "unconnected-(U1-C14-Pad68)") (class "Default")
      (node (ref "U1") (pin "68") (pinfunction "C14_68") (pintype "passive+no_connect"))
    )
    (net (code "91") (name "unconnected-(U1-C15-Pad65)") (class "Default")
      (node (ref "U1") (pin "65") (pinfunction "C15_65") (pintype "passive+no_connect"))
    )
    (net (code "92") (name "unconnected-(U1-C16-Pad66)") (class "Default")
      (node (ref "U1") (pin "66") (pinfunction "C16_66") (pintype "passive+no_connect"))
    )
    (net (code "93") (name "unconnected-(U1-C17-Pad63)") (class "Default")
      (node (ref "U1") (pin "63") (pinfunction "C17_63") (pintype "passive+no_connect"))
    )
    (net (code "94") (name "unconnected-(U1-C20-Pad62)") (class "Default")
      (node (ref "U1") (pin "62") (pinfunction "C20_62") (pintype "passive+no_connect"))
    )
    (net (code "95") (name "unconnected-(U1-C21-Pad59)") (class "Default")
      (node (ref "U1") (pin "59") (pinfunction "C21_59") (pintype "passive+no_connect"))
    )
    (net (code "96") (name "unconnected-(U1-C22-Pad60)") (class "Default")
      (node (ref "U1") (pin "60") (pinfunction "C22_60") (pintype "passive+no_connect"))
    )
    (net (code "97") (name "unconnected-(U1-D4-Pad10)") (class "Default")
      (node (ref "U1") (pin "10") (pinfunction "D4_10") (pintype "passive"))
    )
    (net (code "98") (name "unconnected-(U1-D14-Pad17)") (class "Default")
      (node (ref "U1") (pin "17") (pinfunction "D14_17") (pintype "passive+no_connect"))
    )
    (net (code "99") (name "unconnected-(U1-D15-Pad18)") (class "Default")
      (node (ref "U1") (pin "18") (pinfunction "D15_18") (pintype "passive+no_connect"))
    )
    (net (code "100") (name "unconnected-(U1-D16-Pad19)") (class "Default")
      (node (ref "U1") (pin "19") (pinfunction "D16_19") (pintype "passive+no_connect"))
    )
    (net (code "101") (name "unconnected-(U1-D17-Pad20)") (class "Default")
      (node (ref "U1") (pin "20") (pinfunction "D17_20") (pintype "passive+no_connect"))
    )
    (net (code "102") (name "unconnected-(U1-D26-Pad84)") (class "Default")
      (node (ref "U1") (pin "84") (pinfunction "D26_84") (pintype "passive+no_connect"))
    )
    (net (code "103") (name "unconnected-(U1-D27-Pad81)") (class "Default")
      (node (ref "U1") (pin "81") (pinfunction "D27_81") (pintype "passive+no_connect"))
    )
    (net (code "104") (name "unconnected-(U1-OF-Pad7)") (class "Default")
      (node (ref "U1") (pin "7") (pinfunction "OF_7") (pintype "passive+no_connect"))
    )
    (net (code "105") (name "unconnected-(U1-WU-Pad8)") (class "Default")
      (node (ref "U1") (pin "8") (pinfunction "WU_8") (pintype "passive+no_connect"))
    )
  )
)
